# icemaker.net
KiCad netlist of a schematic drawn in EAGLE
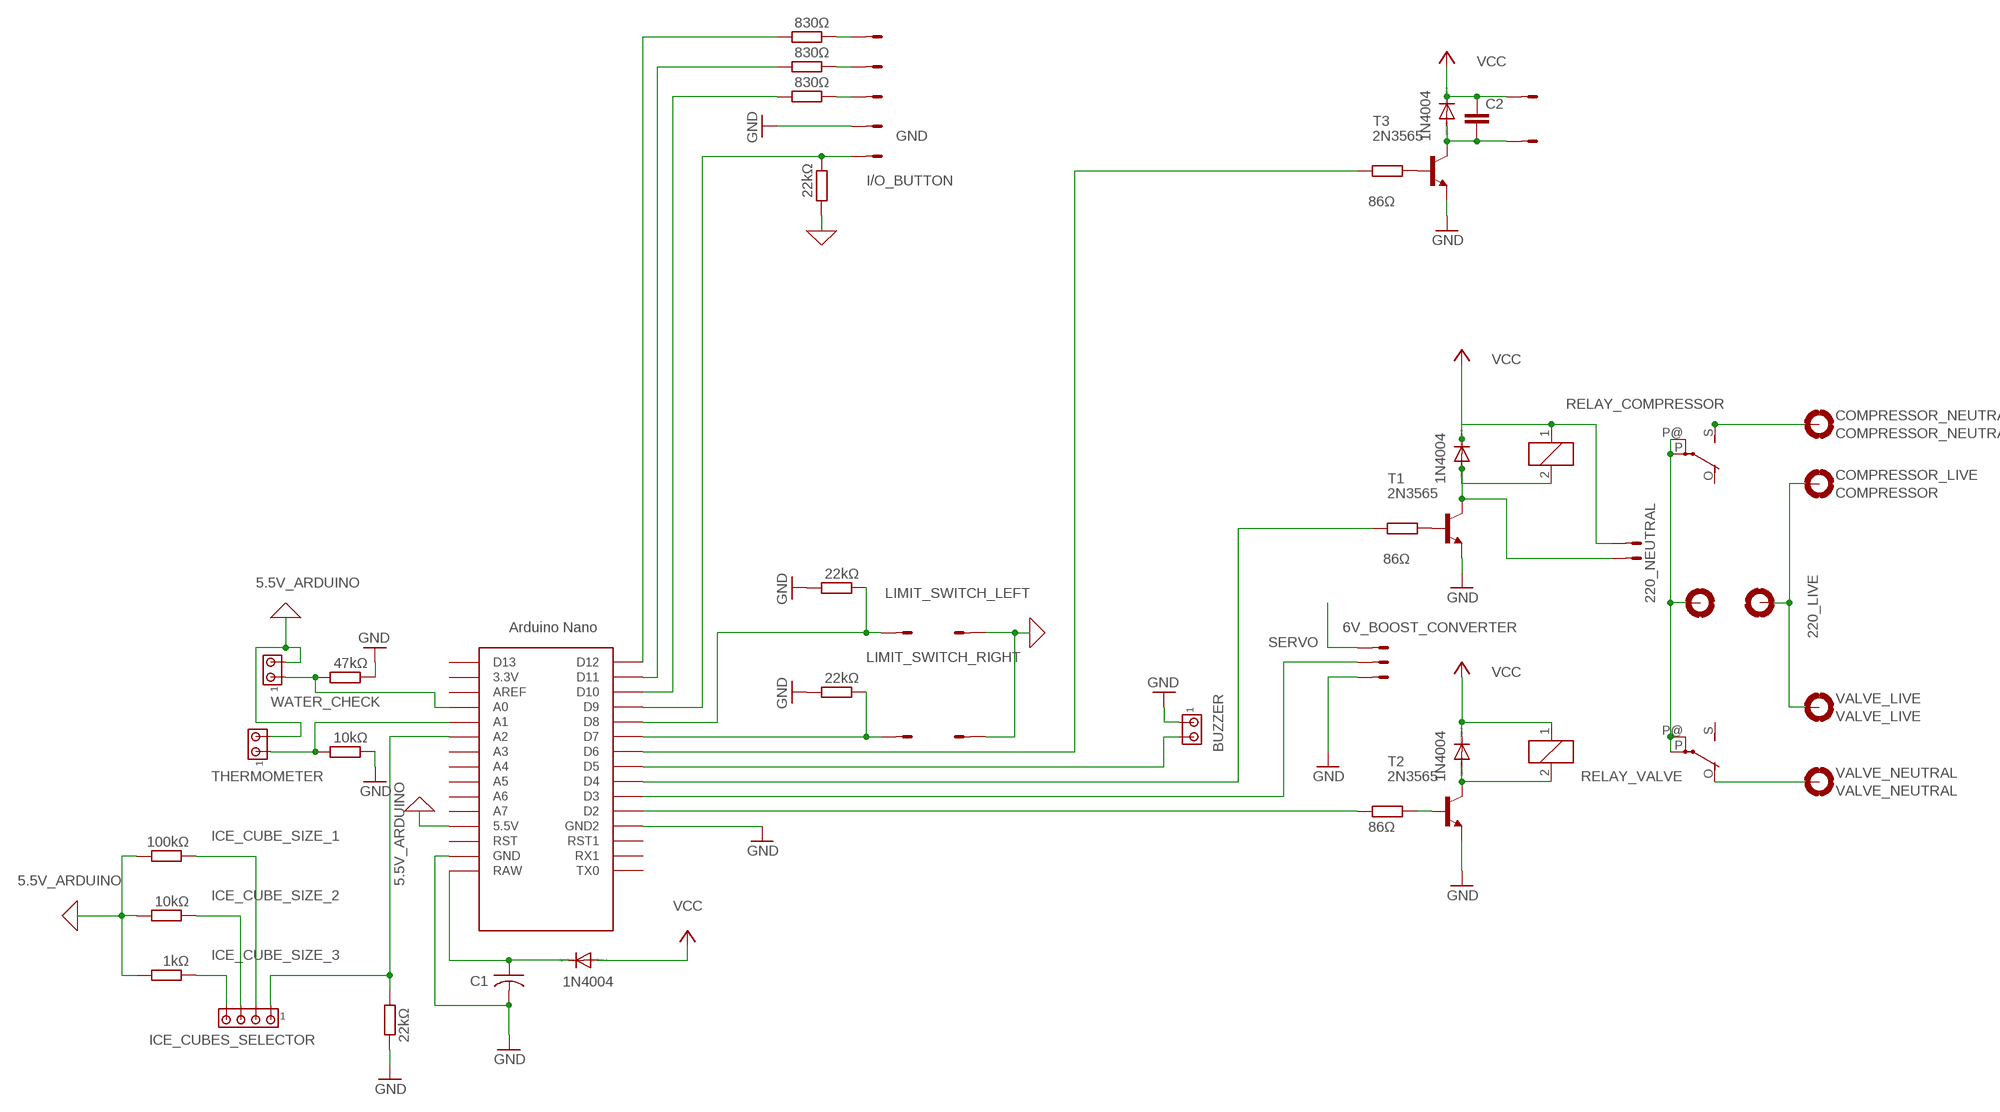
[diagram p0: schematic, sheet 1]

(export (version "E")
  (design (tool "Eeschema 10.0.6"))
  (components
    (comp (ref "220_LIVE")
      (value "220_LIVE")
      (footprint "eagle-import:2,8-PAD")
      (libsource (lib "eagle-import") (part "MOUNT-PAD-ROUND2.8"))
    )
    (comp (ref "220_NEUTRLA")
      (value "220_NEUTRAL")
      (footprint "eagle-import:2,8-PAD")
      (libsource (lib "eagle-import") (part "MOUNT-PAD-ROUND2.8"))
    )
    (comp (ref "BUZZER")
      (value "MTA02-156")
      (footprint "eagle-import:1X2MTA")
      (libsource (lib "eagle-import") (part "MTA02-156"))
    )
    (comp (ref "C1")
      (value "C-US050-025X075")
      (footprint "eagle-import:C050-025X075")
      (libsource (lib "eagle-import") (part "C-US050-025X075"))
    )
    (comp (ref "C2")
      (value "C2,5-3")
      (footprint "eagle-import:C2.5-3")
      (libsource (lib "eagle-import") (part "C2,5-3"))
    )
    (comp (ref "COMPRESSOR_LIVE")
      (value "COMPRESSOR")
      (footprint "eagle-import:2,8-PAD")
      (libsource (lib "eagle-import") (part "MOUNT-PAD-ROUND2.8"))
    )
    (comp (ref "COMPRESSOR_NEUTRAL")
      (value "COMPRESSOR_NEUTRAL")
      (footprint "eagle-import:2,8-PAD")
      (libsource (lib "eagle-import") (part "MOUNT-PAD-ROUND2.8"))
    )
    (comp (ref "D1")
      (value "1N4004")
      (footprint "eagle-import:DO41-10")
      (libsource (lib "eagle-import") (part "1N4004"))
    )
    (comp (ref "D2")
      (value "1N4004")
      (footprint "eagle-import:DO41-10")
      (libsource (lib "eagle-import") (part "1N4004"))
    )
    (comp (ref "D3")
      (value "1N4004")
      (footprint "eagle-import:DO41-10")
      (libsource (lib "eagle-import") (part "1N4004"))
    )
    (comp (ref "D4")
      (value "1N4004")
      (footprint "eagle-import:DO41-10")
      (libsource (lib "eagle-import") (part "1N4004"))
    )
    (comp (ref "FAN")
      (value "L02P")
      (footprint "eagle-import:L02P")
      (libsource (lib "eagle-import") (part "L02P"))
    )
    (comp (ref "ICE_CUBES_SELECTOR")
      (value "MTA04-156")
      (footprint "eagle-import:1X4MTA")
      (libsource (lib "eagle-import") (part "MTA04-156"))
    )
    (comp (ref "LED_WORK")
      (value "I/O_BUTTON")
      (footprint "eagle-import:L05P")
      (libsource (lib "eagle-import") (part "L05P"))
    )
    (comp (ref "PUMP")
      (value "L02P")
      (footprint "eagle-import:L02P")
      (libsource (lib "eagle-import") (part "L02P"))
    )
    (comp (ref "R1")
      (value "86Ω")
      (footprint "eagle-import:0204_5")
      (libsource (lib "eagle-import") (part "R-EU_0204/5"))
    )
    (comp (ref "R2")
      (value "86Ω")
      (footprint "eagle-import:0204_5")
      (libsource (lib "eagle-import") (part "R-EU_0204/5"))
    )
    (comp (ref "R3")
      (value "86Ω")
      (footprint "eagle-import:0204_5")
      (libsource (lib "eagle-import") (part "R-EU_0204/5"))
    )
    (comp (ref "R4")
      (value "1kΩ")
      (footprint "eagle-import:0204_5")
      (libsource (lib "eagle-import") (part "R-EU_0204/5"))
    )
    (comp (ref "R5")
      (value "47kΩ")
      (footprint "eagle-import:0204_5")
      (libsource (lib "eagle-import") (part "R-EU_0204/5"))
    )
    (comp (ref "R6")
      (value "10kΩ")
      (footprint "eagle-import:0204_5")
      (libsource (lib "eagle-import") (part "R-EU_0204/5"))
    )
    (comp (ref "R7")
      (value "830Ω")
      (footprint "eagle-import:0204_5")
      (libsource (lib "eagle-import") (part "R-EU_0204/5"))
    )
    (comp (ref "R8")
      (value "830Ω")
      (footprint "eagle-import:0204_5")
      (libsource (lib "eagle-import") (part "R-EU_0204/5"))
    )
    (comp (ref "R9")
      (value "830Ω")
      (footprint "eagle-import:0204_5")
      (libsource (lib "eagle-import") (part "R-EU_0204/5"))
    )
    (comp (ref "R10")
      (value "22kΩ")
      (footprint "eagle-import:0204_5")
      (libsource (lib "eagle-import") (part "R-EU_0204/5"))
    )
    (comp (ref "R11")
      (value "22kΩ")
      (footprint "eagle-import:0204_5")
      (libsource (lib "eagle-import") (part "R-EU_0204/5"))
    )
    (comp (ref "R12")
      (value "22kΩ")
      (footprint "eagle-import:0204_5")
      (libsource (lib "eagle-import") (part "R-EU_0204/5"))
    )
    (comp (ref "R13")
      (value "10kΩ")
      (footprint "eagle-import:0204_5")
      (libsource (lib "eagle-import") (part "R-EU_0204/5"))
    )
    (comp (ref "R14")
      (value "100kΩ")
      (footprint "eagle-import:0204_5")
      (libsource (lib "eagle-import") (part "R-EU_0204/5"))
    )
    (comp (ref "R16")
      (value "22kΩ")
      (footprint "eagle-import:0204_5")
      (libsource (lib "eagle-import") (part "R-EU_0204/5"))
    )
    (comp (ref "RELAY_COMPRESSOR")
      (value "M3XXH")
      (footprint "eagle-import:M3XXH")
      (libsource (lib "eagle-import") (part "M3XXH"))
    )
    (comp (ref "RELAY_VALVE")
      (value "M3XXH")
      (footprint "eagle-import:M3XXH")
      (libsource (lib "eagle-import") (part "M3XXH"))
    )
    (comp (ref "SERVO")
      (value "S03P")
      (footprint "eagle-import:S03P")
      (libsource (lib "eagle-import") (part "S03P"))
    )
    (comp (ref "SV1")
      (value "L04P")
      (footprint "eagle-import:L04P")
      (libsource (lib "eagle-import") (part "L04P"))
    )
    (comp (ref "T1")
      (value "2N3565")
      (footprint "eagle-import:TO92")
      (libsource (lib "eagle-import") (part "2N3565"))
    )
    (comp (ref "T2")
      (value "2N3565")
      (footprint "eagle-import:TO92")
      (libsource (lib "eagle-import") (part "2N3565"))
    )
    (comp (ref "T3")
      (value "2N3565")
      (footprint "eagle-import:TO92")
      (libsource (lib "eagle-import") (part "2N3565"))
    )
    (comp (ref "THERMOMETER")
      (value "MTA02-156")
      (footprint "eagle-import:1X2MTA")
      (libsource (lib "eagle-import") (part "MTA02-156"))
    )
    (comp (ref "U$1")
      (value "NANO")
      (footprint "eagle-import:NANO")
      (libsource (lib "eagle-import") (part "NANO"))
    )
    (comp (ref "VALVE_LIVE")
      (value "VALVE_LIVE")
      (footprint "eagle-import:2,8-PAD")
      (libsource (lib "eagle-import") (part "MOUNT-PAD-ROUND2.8"))
    )
    (comp (ref "VALVE_NEUTRAL")
      (value "VALVE_NEUTRAL")
      (footprint "eagle-import:2,8-PAD")
      (libsource (lib "eagle-import") (part "MOUNT-PAD-ROUND2.8"))
    )
    (comp (ref "WATER_CHECK")
      (value "MTA02-156")
      (footprint "eagle-import:1X2MTA")
      (libsource (lib "eagle-import") (part "MTA02-156"))
    )
  )
  (nets
    (net (code "1") (name "/6V_BOOST_CONVERTER") (class "Default")
      (node (ref "SERVO") (pin "3") (pinfunction "S_3") (pintype "passive"))
    )
    (net (code "2") (name "/220_NEUTRAL") (class "Default")
      (node (ref "220_NEUTRLA") (pin "B2,8") (pinfunction "MOUNT_B2,8") (pintype "passive"))
      (node (ref "RELAY_COMPRESSOR") (pin "P") (pinfunction "P_P") (pintype "passive"))
      (node (ref "RELAY_COMPRESSOR") (pin "P@") (pinfunction "P_P@") (pintype "passive"))
      (node (ref "RELAY_VALVE") (pin "P") (pinfunction "P_P") (pintype "passive"))
      (node (ref "RELAY_VALVE") (pin "P@") (pinfunction "P_P@") (pintype "passive"))
    )
    (net (code "3") (name "/BUZZER") (class "Default")
      (node (ref "BUZZER") (pin "2") (pinfunction "2_2") (pintype "passive"))
      (node (ref "U$1") (pin "D5") (pinfunction "D5_D5") (pintype "bidirectional"))
    )
    (net (code "4") (name "/ICE_CUBE_SIZE_1") (class "Default")
      (node (ref "ICE_CUBES_SELECTOR") (pin "2") (pinfunction "2_2") (pintype "passive"))
      (node (ref "R14") (pin "1") (pinfunction "1_1") (pintype "passive"))
    )
    (net (code "5") (name "/ICE_CUBE_SIZE_2") (class "Default")
      (node (ref "ICE_CUBES_SELECTOR") (pin "3") (pinfunction "3_3") (pintype "passive"))
      (node (ref "R13") (pin "1") (pinfunction "1_1") (pintype "passive"))
    )
    (net (code "6") (name "/ICE_CUBE_SIZE_3") (class "Default")
      (node (ref "ICE_CUBES_SELECTOR") (pin "4") (pinfunction "4_4") (pintype "passive"))
      (node (ref "R4") (pin "1") (pinfunction "1_1") (pintype "passive"))
    )
    (net (code "7") (name "/I{slash}O_BUTTON") (class "Default")
      (node (ref "LED_WORK") (pin "1") (pinfunction "S_1") (pintype "passive"))
      (node (ref "R10") (pin "1") (pinfunction "1_1") (pintype "passive"))
      (node (ref "U$1") (pin "D9") (pinfunction "D9_D9") (pintype "bidirectional"))
    )
    (net (code "8") (name "/LIMIT_SWITCH_LEFT") (class "Default")
      (node (ref "R11") (pin "1") (pinfunction "1_1") (pintype "passive"))
      (node (ref "SV1") (pin "4") (pinfunction "S_4") (pintype "passive"))
      (node (ref "U$1") (pin "D8") (pinfunction "D8_D8") (pintype "bidirectional"))
    )
    (net (code "9") (name "/LIMIT_SWITCH_RIGHT") (class "Default")
      (node (ref "R12") (pin "1") (pinfunction "1_1") (pintype "passive"))
      (node (ref "SV1") (pin "1") (pinfunction "S_1") (pintype "passive"))
      (node (ref "U$1") (pin "D7") (pinfunction "D7_D7") (pintype "bidirectional"))
    )
    (net (code "10") (name "/SERVO") (class "Default")
      (node (ref "SERVO") (pin "2") (pinfunction "S_2") (pintype "passive"))
      (node (ref "U$1") (pin "D3") (pinfunction "D3_D3") (pintype "bidirectional"))
    )
    (net (code "11") (name "/THERMOMETER") (class "Default")
      (node (ref "R6") (pin "2") (pinfunction "2_2") (pintype "passive"))
      (node (ref "THERMOMETER") (pin "1") (pinfunction "1_1") (pintype "passive"))
      (node (ref "U$1") (pin "A1") (pinfunction "A1_A1") (pintype "bidirectional"))
    )
    (net (code "12") (name "/WATER_CHECK") (class "Default")
      (node (ref "R5") (pin "2") (pinfunction "2_2") (pintype "passive"))
      (node (ref "U$1") (pin "A0") (pinfunction "A0_A0") (pintype "bidirectional"))
      (node (ref "WATER_CHECK") (pin "1") (pinfunction "1_1") (pintype "passive"))
    )
    (net (code "13") (name "5.5V_ARDUINO") (class "Default")
      (node (ref "R10") (pin "2") (pinfunction "2_2") (pintype "passive"))
      (node (ref "R13") (pin "2") (pinfunction "2_2") (pintype "passive"))
      (node (ref "R14") (pin "2") (pinfunction "2_2") (pintype "passive"))
      (node (ref "R4") (pin "2") (pinfunction "2_2") (pintype "passive"))
      (node (ref "SV1") (pin "2") (pinfunction "S_2") (pintype "passive"))
      (node (ref "SV1") (pin "3") (pinfunction "S_3") (pintype "passive"))
      (node (ref "THERMOMETER") (pin "2") (pinfunction "2_2") (pintype "passive"))
      (node (ref "U$1") (pin "5V") (pinfunction "5.5V_5V") (pintype "bidirectional"))
      (node (ref "WATER_CHECK") (pin "2") (pinfunction "2_2") (pintype "passive"))
    )
    (net (code "14") (name "GND") (class "Default")
      (node (ref "BUZZER") (pin "1") (pinfunction "1_1") (pintype "passive"))
      (node (ref "C1") (pin "2") (pinfunction "2_2") (pintype "passive"))
      (node (ref "LED_WORK") (pin "2") (pinfunction "S_2") (pintype "passive"))
      (node (ref "R11") (pin "2") (pinfunction "2_2") (pintype "passive"))
      (node (ref "R12") (pin "2") (pinfunction "2_2") (pintype "passive"))
      (node (ref "R16") (pin "1") (pinfunction "1_1") (pintype "passive"))
      (node (ref "R5") (pin "1") (pinfunction "1_1") (pintype "passive"))
      (node (ref "R6") (pin "1") (pinfunction "1_1") (pintype "passive"))
      (node (ref "SERVO") (pin "1") (pinfunction "S_1") (pintype "passive"))
      (node (ref "T1") (pin "3") (pinfunction "E_3") (pintype "passive"))
      (node (ref "T2") (pin "3") (pinfunction "E_3") (pintype "passive"))
      (node (ref "T3") (pin "3") (pinfunction "E_3") (pintype "passive"))
      (node (ref "U$1") (pin "GND") (pinfunction "GND_GND") (pintype "bidirectional"))
      (node (ref "U$1") (pin "GND1") (pinfunction "GND2_GND1") (pintype "bidirectional"))
    )
    (net (code "15") (name "Net-(220_LIVE-MOUNT)") (class "Default")
      (node (ref "220_LIVE") (pin "B2,8") (pinfunction "MOUNT_B2,8") (pintype "passive"))
      (node (ref "COMPRESSOR_LIVE") (pin "B2,8") (pinfunction "MOUNT_B2,8") (pintype "passive"))
      (node (ref "VALVE_LIVE") (pin "B2,8") (pinfunction "MOUNT_B2,8") (pintype "passive"))
    )
    (net (code "16") (name "Net-(C1-Pad1)") (class "Default")
      (node (ref "C1") (pin "1") (pinfunction "1_1") (pintype "passive"))
      (node (ref "D3") (pin "C") (pinfunction "C_C") (pintype "passive"))
      (node (ref "U$1") (pin "RAW") (pinfunction "RAW_RAW") (pintype "bidirectional"))
    )
    (net (code "17") (name "Net-(COMPRESSOR_NEUTRAL-MOUNT)") (class "Default")
      (node (ref "COMPRESSOR_NEUTRAL") (pin "B2,8") (pinfunction "MOUNT_B2,8") (pintype "passive"))
      (node (ref "RELAY_COMPRESSOR") (pin "S") (pinfunction "S_S") (pintype "passive"))
    )
    (net (code "18") (name "Net-(FANA-S)") (class "Default")
      (node (ref "D2") (pin "A") (pinfunction "A_A") (pintype "passive"))
      (node (ref "FAN") (pin "1") (pinfunction "S_1") (pintype "passive"))
      (node (ref "RELAY_COMPRESSOR") (pin "2") (pinfunction "2_2") (pintype "passive"))
      (node (ref "T1") (pin "1") (pinfunction "C_1") (pintype "passive"))
    )
    (net (code "19") (name "Net-(ICE_CUBES_SELECTOR-Pad1)") (class "Default")
      (node (ref "ICE_CUBES_SELECTOR") (pin "1") (pinfunction "1_1") (pintype "passive"))
      (node (ref "R16") (pin "2") (pinfunction "2_2") (pintype "passive"))
      (node (ref "U$1") (pin "A2") (pinfunction "A2_A2") (pintype "bidirectional"))
    )
    (net (code "20") (name "Net-(LED_WORKC-S)") (class "Default")
      (node (ref "LED_WORK") (pin "3") (pinfunction "S_3") (pintype "passive"))
      (node (ref "R9") (pin "1") (pinfunction "1_1") (pintype "passive"))
    )
    (net (code "21") (name "Net-(LED_WORKD-S)") (class "Default")
      (node (ref "LED_WORK") (pin "4") (pinfunction "S_4") (pintype "passive"))
      (node (ref "R8") (pin "1") (pinfunction "1_1") (pintype "passive"))
    )
    (net (code "22") (name "Net-(LED_WORKE-S)") (class "Default")
      (node (ref "LED_WORK") (pin "5") (pinfunction "S_5") (pintype "passive"))
      (node (ref "R7") (pin "1") (pinfunction "1_1") (pintype "passive"))
    )
    (net (code "23") (name "Net-(PUMPA-S)") (class "Default")
      (node (ref "C2") (pin "2") (pinfunction "2_2") (pintype "passive"))
      (node (ref "D4") (pin "A") (pinfunction "A_A") (pintype "passive"))
      (node (ref "PUMP") (pin "1") (pinfunction "S_1") (pintype "passive"))
      (node (ref "T3") (pin "1") (pinfunction "C_1") (pintype "passive"))
    )
    (net (code "24") (name "Net-(R1-Pad2)") (class "Default")
      (node (ref "R1") (pin "2") (pinfunction "2_2") (pintype "passive"))
      (node (ref "U$1") (pin "D4") (pinfunction "D4_D4") (pintype "bidirectional"))
    )
    (net (code "25") (name "Net-(R2-Pad2)") (class "Default")
      (node (ref "R2") (pin "2") (pinfunction "2_2") (pintype "passive"))
      (node (ref "U$1") (pin "D6") (pinfunction "D6_D6") (pintype "bidirectional"))
    )
    (net (code "26") (name "Net-(R3-Pad2)") (class "Default")
      (node (ref "R3") (pin "2") (pinfunction "2_2") (pintype "passive"))
      (node (ref "U$1") (pin "D2") (pinfunction "D2_D2") (pintype "bidirectional"))
    )
    (net (code "27") (name "Net-(R7-Pad2)") (class "Default")
      (node (ref "R7") (pin "2") (pinfunction "2_2") (pintype "passive"))
      (node (ref "U$1") (pin "D12") (pinfunction "D12_D12") (pintype "bidirectional"))
    )
    (net (code "28") (name "Net-(R8-Pad2)") (class "Default")
      (node (ref "R8") (pin "2") (pinfunction "2_2") (pintype "passive"))
      (node (ref "U$1") (pin "D11") (pinfunction "D11_D11") (pintype "bidirectional"))
    )
    (net (code "29") (name "Net-(R9-Pad2)") (class "Default")
      (node (ref "R9") (pin "2") (pinfunction "2_2") (pintype "passive"))
      (node (ref "U$1") (pin "D10") (pinfunction "D10_D10") (pintype "bidirectional"))
    )
    (net (code "30") (name "Net-(T1-B)") (class "Default")
      (node (ref "R1") (pin "1") (pinfunction "1_1") (pintype "passive"))
      (node (ref "T1") (pin "2") (pinfunction "B_2") (pintype "passive"))
    )
    (net (code "31") (name "Net-(T2-B)") (class "Default")
      (node (ref "R3") (pin "1") (pinfunction "1_1") (pintype "passive"))
      (node (ref "T2") (pin "2") (pinfunction "B_2") (pintype "passive"))
    )
    (net (code "32") (name "Net-(T2-C)") (class "Default")
      (node (ref "D1") (pin "A") (pinfunction "A_A") (pintype "passive"))
      (node (ref "RELAY_VALVE") (pin "2") (pinfunction "2_2") (pintype "passive"))
      (node (ref "T2") (pin "1") (pinfunction "C_1") (pintype "passive"))
    )
    (net (code "33") (name "Net-(T3-B)") (class "Default")
      (node (ref "R2") (pin "1") (pinfunction "1_1") (pintype "passive"))
      (node (ref "T3") (pin "2") (pinfunction "B_2") (pintype "passive"))
    )
    (net (code "34") (name "Net-(VALVE_NEUTRAL-MOUNT)") (class "Default")
      (node (ref "RELAY_VALVE") (pin "O") (pinfunction "O_O") (pintype "passive"))
      (node (ref "VALVE_NEUTRAL") (pin "B2,8") (pinfunction "MOUNT_B2,8") (pintype "passive"))
    )
    (net (code "35") (name "VCC") (class "Default")
      (node (ref "C2") (pin "1") (pinfunction "1_1") (pintype "passive"))
      (node (ref "D1") (pin "C") (pinfunction "C_C") (pintype "passive"))
      (node (ref "D2") (pin "C") (pinfunction "C_C") (pintype "passive"))
      (node (ref "D3") (pin "A") (pinfunction "A_A") (pintype "passive"))
      (node (ref "D4") (pin "C") (pinfunction "C_C") (pintype "passive"))
      (node (ref "FAN") (pin "2") (pinfunction "S_2") (pintype "passive"))
      (node (ref "PUMP") (pin "2") (pinfunction "S_2") (pintype "passive"))
      (node (ref "RELAY_COMPRESSOR") (pin "1") (pinfunction "1_1") (pintype "passive"))
      (node (ref "RELAY_VALVE") (pin "1") (pinfunction "1_1") (pintype "passive"))
    )
    (net (code "36") (name "unconnected-(RELAY_COMPRESSOR-PadO)") (class "Default")
      (node (ref "RELAY_COMPRESSOR") (pin "O") (pinfunction "O_O") (pintype "passive"))
    )
    (net (code "37") (name "unconnected-(RELAY_VALVE-PadS)") (class "Default")
      (node (ref "RELAY_VALVE") (pin "S") (pinfunction "S_S") (pintype "passive"))
    )
    (net (code "38") (name "unconnected-(U$1-Pad3.3V)") (class "Default")
      (node (ref "U$1") (pin "3.3V") (pinfunction "3.3V_3.3V") (pintype "bidirectional"))
    )
    (net (code "39") (name "unconnected-(U$1-PadA3)") (class "Default")
      (node (ref "U$1") (pin "A3") (pinfunction "A3_A3") (pintype "bidirectional"))
    )
    (net (code "40") (name "unconnected-(U$1-PadA4)") (class "Default")
      (node (ref "U$1") (pin "A4") (pinfunction "A4_A4") (pintype "bidirectional"))
    )
    (net (code "41") (name "unconnected-(U$1-PadA5)") (class "Default")
      (node (ref "U$1") (pin "A5") (pinfunction "A5_A5") (pintype "bidirectional"))
    )
    (net (code "42") (name "unconnected-(U$1-PadA6)") (class "Default")
      (node (ref "U$1") (pin "A6") (pinfunction "A6_A6") (pintype "bidirectional"))
    )
    (net (code "43") (name "unconnected-(U$1-PadA7)") (class "Default")
      (node (ref "U$1") (pin "A7") (pinfunction "A7_A7") (pintype "bidirectional"))
    )
    (net (code "44") (name "unconnected-(U$1-PadAREF)") (class "Default")
      (node (ref "U$1") (pin "AREF") (pinfunction "AREF_AREF") (pintype "bidirectional"))
    )
    (net (code "45") (name "unconnected-(U$1-PadD13)") (class "Default")
      (node (ref "U$1") (pin "D13") (pinfunction "D13_D13") (pintype "bidirectional"))
    )
    (net (code "46") (name "unconnected-(U$1-PadICSP1)") (class "Default")
      (node (ref "U$1") (pin "ICSP1") (pinfunction "ICSP1_ICSP1") (pintype "bidirectional"))
    )
    (net (code "47") (name "unconnected-(U$1-PadICSP2)") (class "Default")
      (node (ref "U$1") (pin "ICSP2") (pinfunction "ICSP2_ICSP2") (pintype "bidirectional"))
    )
    (net (code "48") (name "unconnected-(U$1-PadICSP3)") (class "Default")
      (node (ref "U$1") (pin "ICSP3") (pinfunction "ICSP3_ICSP3") (pintype "bidirectional"))
    )
    (net (code "49") (name "unconnected-(U$1-PadICSP4)") (class "Default")
      (node (ref "U$1") (pin "ICSP4") (pinfunction "ICSP4_ICSP4") (pintype "bidirectional"))
    )
    (net (code "50") (name "unconnected-(U$1-PadICSP5)") (class "Default")
      (node (ref "U$1") (pin "ICSP5") (pinfunction "ICSP5_ICSP5") (pintype "bidirectional"))
    )
    (net (code "51") (name "unconnected-(U$1-PadICSP6)") (class "Default")
      (node (ref "U$1") (pin "ICSP6") (pinfunction "ICSP6_ICSP6") (pintype "bidirectional"))
    )
    (net (code "52") (name "unconnected-(U$1-PadRST)") (class "Default")
      (node (ref "U$1") (pin "RST") (pinfunction "RST_RST") (pintype "bidirectional"))
    )
    (net (code "53") (name "unconnected-(U$1-PadRST1)") (class "Default")
      (node (ref "U$1") (pin "RST1") (pinfunction "RST1_RST1") (pintype "bidirectional"))
    )
    (net (code "54") (name "unconnected-(U$1-PadRX1)") (class "Default")
      (node (ref "U$1") (pin "RX1") (pinfunction "RX1_RX1") (pintype "bidirectional"))
    )
    (net (code "55") (name "unconnected-(U$1-PadTX0)") (class "Default")
      (node (ref "U$1") (pin "TX0") (pinfunction "TX0_TX0") (pintype "bidirectional"))
    )
  )
)
